# MIXR_Input_System_-_input.net
KiCad netlist of a schematic drawn in Altium Designer
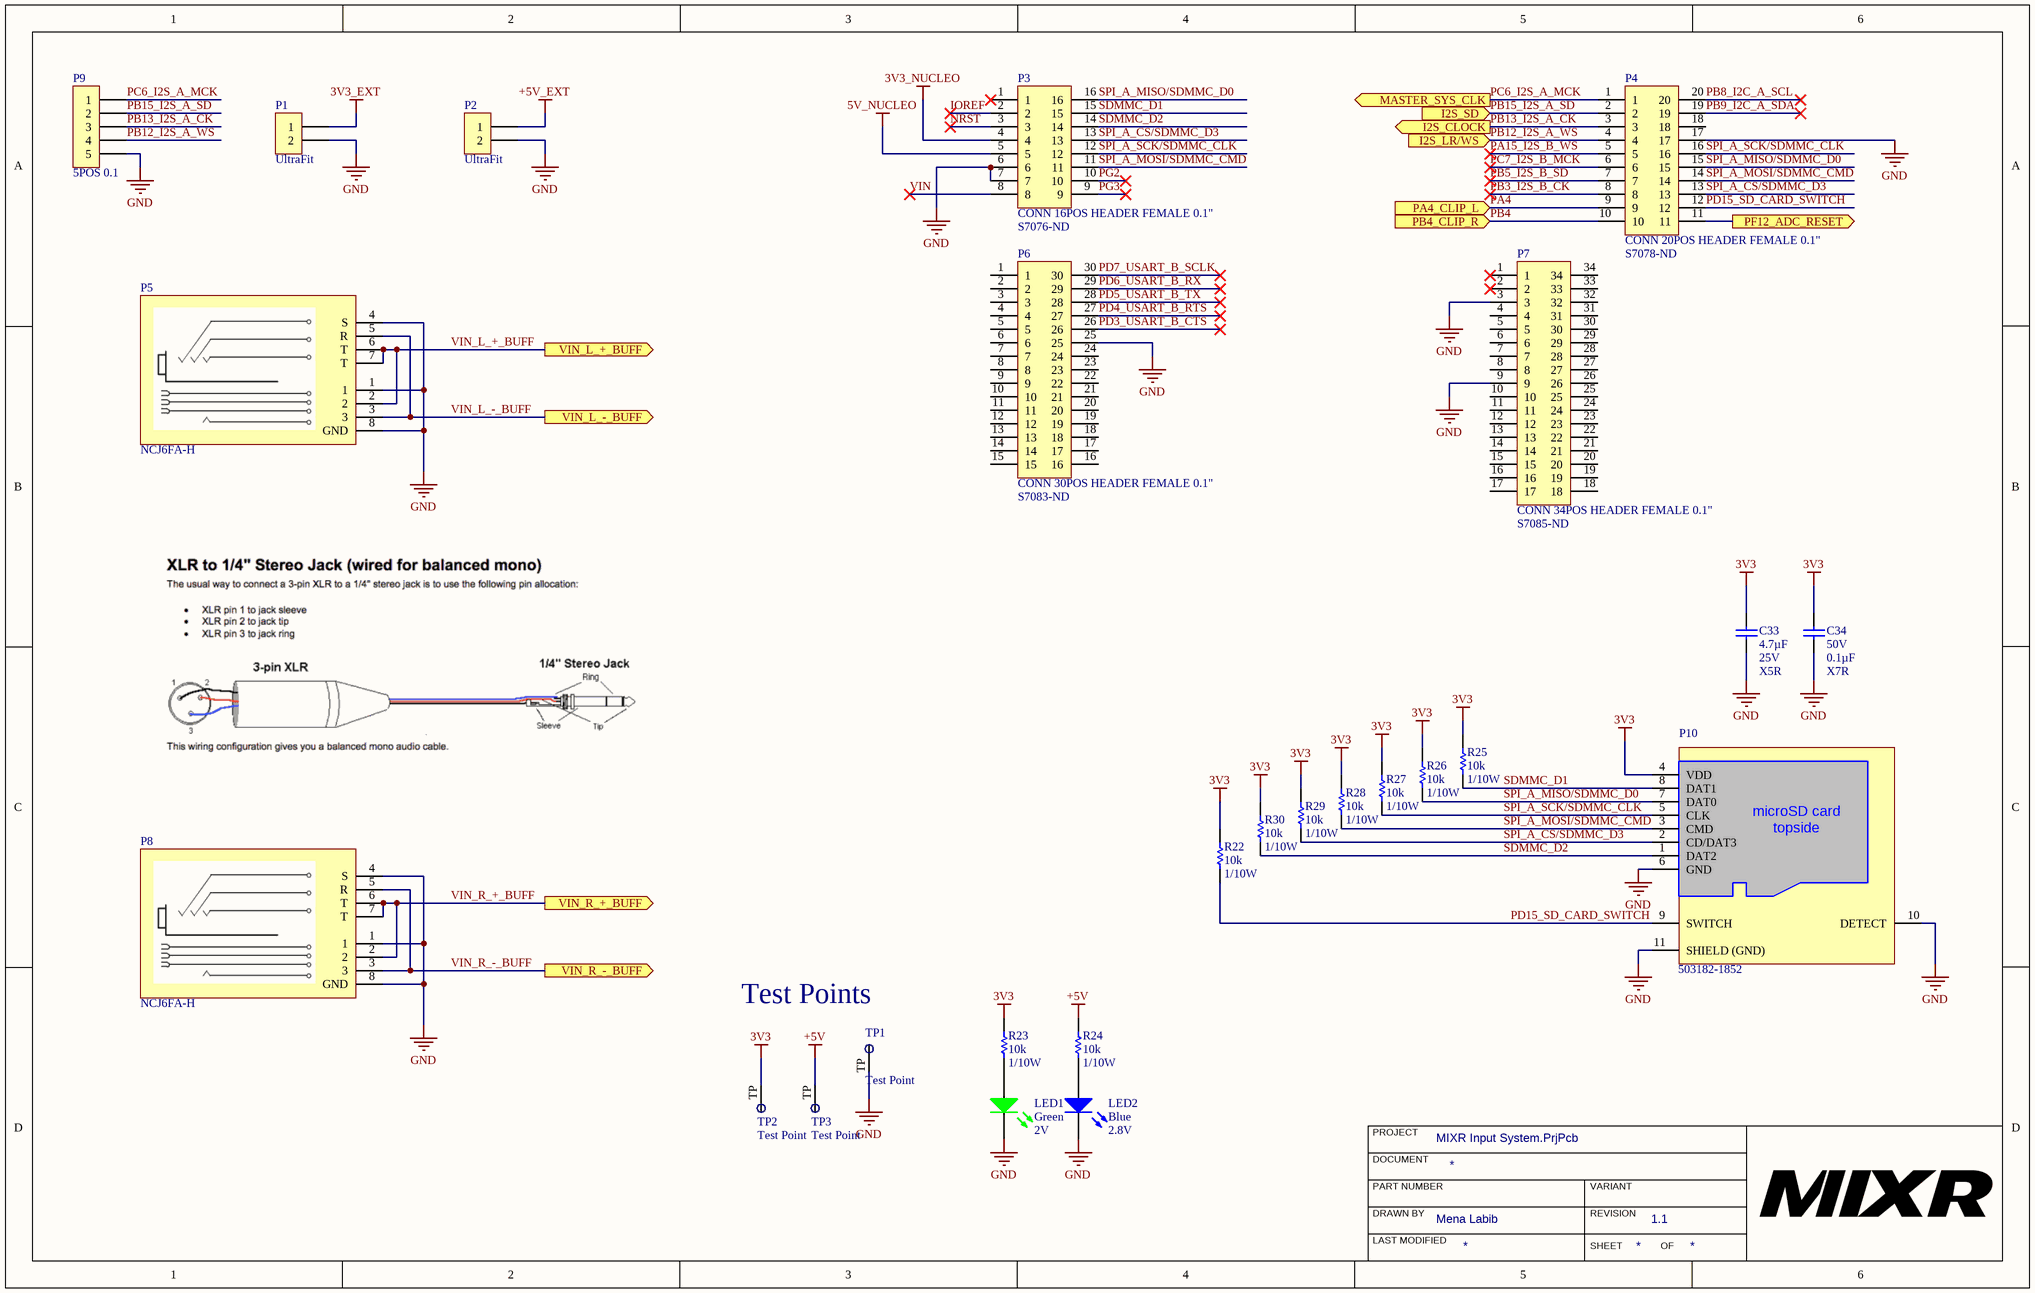
[diagram p0: MIXR Input System - input.SchDoc]

(export (version "E")
  (design (tool "Eeschema 10.0.6"))
  (components
    (comp (ref "C33")
      (value "CAP CER 4.7UF 25V 10% X5R 0603")
      (footprint "CAP, 0603")
      (description "4.7µF ±10% 25V Ceramic Capacitor X5R 0603 (1608 Metric)")
      (fields
        (field (name "TOLERANCE") "±10%")
        (field (name "CAPACITANCE") "4.7µF")
        (field (name "VOLTAGE") "25V")
        (field (name "TEMPERATURE COEFFICIENT") "X5R")
      )
      (libsource (lib "Schematic Diagrams") (part "CAP CER 4.7UF 25V 10% X5R 0603"))
    )
    (comp (ref "C34")
      (value "CAP CER 0.1UF 50V 10% X7R 0603")
      (footprint "CAP, 0603")
      (description "0.10µF ±10% 50V Ceramic Capacitor X7R 0603 (1608 Metric)")
      (fields
        (field (name "VOLTAGE") "50V")
        (field (name "TOLERANCE") "±10%")
        (field (name "CAPACITANCE") "0.1µF")
        (field (name "TEMPERATURE COEFFICIENT") "X7R")
      )
      (libsource (lib "Schematic Diagrams") (part "CAP CER 0.1UF 50V 10% X7R 0603"))
    )
    (comp (ref "LED1")
      (value "LED GREEN CLEAR 2V 0603")
      (footprint "LED_0603")
      (description "Green 572nm LED Indication - Discrete 2V 0603 (1608 Metric)")
      (fields
        (field (name "MANUFACTURER") "Wurth Electronics Inc.")
        (field (name "MANUFACTURER PART NUMBER") "150060VS75000")
        (field (name "COLOR") "Green")
        (field (name "VOLTAGE - FORWARD (VF) (TYP)") "2V")
      )
      (libsource (lib "Schematic Diagrams") (part "LED GREEN CLEAR 2V 0603"))
    )
    (comp (ref "LED2")
      (value "LED BLUE CLEAR 2.8V 0603")
      (footprint "LED_0603")
      (description "Blue 470nm LED Indication - Discrete 2.8V 0603 (1608 Metric)")
      (fields (field (name "COLOR") "Blue") (field (name "VOLTAGE - FORWARD (VF) (TYP)") "2.8V"))
      (libsource (lib "Schematic Diagrams") (part "LED BLUE CLEAR 2.8V 0603"))
    )
    (comp (ref "P1")
      (value "CONN 2POS ULTRA-FIT 0.138\"")
      (footprint "CONN, 2POS ULTRA-FIT")
      (description "Connector Header Through Hole 2 position 0.138\" (3.50mm)")
      (fields
        (field (name "MANUFACTURER") "Molex")
        (field (name "MANUFACTURER PART NUMBER") "1722871102")
        (field (name "SERIES") "UltraFit")
      )
      (libsource (lib "Schematic Diagrams") (part "CONN 2POS ULTRA-FIT 0.138{dblquote}"))
    )
    (comp (ref "P2")
      (value "CONN 2POS ULTRA-FIT 0.138\"")
      (footprint "CONN, 2POS ULTRA-FIT")
      (description "Connector Header Through Hole 2 position 0.138\" (3.50mm)")
      (fields
        (field (name "MANUFACTURER") "Molex")
        (field (name "MANUFACTURER PART NUMBER") "1722871102")
        (field (name "SERIES") "UltraFit")
      )
      (libsource (lib "Schematic Diagrams") (part "CONN 2POS ULTRA-FIT 0.138{dblquote}"))
    )
    (comp (ref "P3")
      (value "CONN 16POS HEADER FEMALE 0.1\"")
      (footprint "CONN, 16POS 0.100\" Header")
      (description "16 Position Header Connector 0.100\" (2.54mm) Through Hole Tin")
      (fields
        (field (name "MANUFACTURER") "Sullins")
        (field (name "MANUFACTURER PART NUMBER") "PPTC082LFBN-RC")
        (field (name "SUPPLIER PART NUMBER 1") "S7076-ND")
      )
      (libsource (lib "Schematic Diagrams") (part "CONN 16POS HEADER FEMALE 0.1{dblquote}"))
    )
    (comp (ref "P4")
      (value "CONN 20POS HEADER FEMALE 0.1\"")
      (footprint "CONN, 20POS 0.100\" HEADER")
      (description "20 Position Header Connector 0.100\" (2.54mm) Through Hole Tin")
      (fields
        (field (name "MANUFACTURER") "Sullins")
        (field (name "MANUFACTURER PART NUMBER") "PPTC102LFBN-RC")
        (field (name "SUPPLIER PART NUMBER 1") "S7078-ND")
      )
      (libsource (lib "Schematic Diagrams") (part "CONN 20POS HEADER FEMALE 0.1{dblquote}"))
    )
    (comp (ref "P5")
      (value "CONN XLR-TRS COMBO 3 POLE")
      (footprint "CONN XLR-TRS COMBO 3 POLE")
      (description "XLR Connectors A SERIES COMBO;3POLE FEM;PCB HOR")
      (fields
        (field (name "MANUFACTURER_PART_NUMBER") "NCJ6FA-H")
        (field (name "MOUSER PART NUMBER") "568-NCJ6FA-H")
        (field (name "MANUFACTURER PART NUMBER") "NCJ6FA-H")
      )
      (libsource (lib "Schematic Diagrams") (part "CONN XLR-TRS COMBO 3 POLE"))
    )
    (comp (ref "P6")
      (value "CONN 30POS HEADER FEMALE 0.1\"")
      (footprint "CONN, 30POS 0.100\" HEADER")
      (description "30 Position Header Connector 0.100\" (2.54mm) Through Hole Tin")
      (fields
        (field (name "MANUFACTURER") "Sullins")
        (field (name "MANUFACTURER PART NUMBER") "PPTC152LFBN-RC")
        (field (name "SUPPLIER PART NUMBER 1") "S7083-ND")
      )
      (libsource (lib "Schematic Diagrams") (part "CONN 30POS HEADER FEMALE 0.1{dblquote}"))
    )
    (comp (ref "P7")
      (value "CONN 34POS HEADER FEMALE 0.1\"")
      (footprint "CONN, 34POS 0.100\" HEADER")
      (description "34 Position Header Connector 0.100\" (2.54mm) Through Hole Tin")
      (fields
        (field (name "MANUFACTURER") "Sullins")
        (field (name "MANUFACTURER PART NUMBER") "PPTC172LFBN-RC")
        (field (name "SUPPLIER PART NUMBER 1") "S7085-ND")
      )
      (libsource (lib "Schematic Diagrams") (part "CONN 34POS HEADER FEMALE 0.1{dblquote}"))
    )
    (comp (ref "P8")
      (value "CONN XLR-TRS COMBO 3 POLE")
      (footprint "CONN XLR-TRS COMBO 3 POLE")
      (description "XLR Connectors A SERIES COMBO;3POLE FEM;PCB HOR")
      (fields
        (field (name "MANUFACTURER_PART_NUMBER") "NCJ6FA-H")
        (field (name "MOUSER PART NUMBER") "568-NCJ6FA-H")
        (field (name "MANUFACTURER PART NUMBER") "NCJ6FA-H")
      )
      (libsource (lib "Schematic Diagrams") (part "CONN XLR-TRS COMBO 3 POLE"))
    )
    (comp (ref "P9")
      (value "5POS 0.1")
      (footprint "CONN, 5POS HEADR 0.1\"")
      (description "5 Positions Header, Breakaway Connector 0.100\" (2.54mm) Through Hole Tin")
      (libsource (lib "Schematic Diagrams") (part "CONN 5POS HEADR MALE 0.1in"))
    )
    (comp (ref "P10")
      (value "CONN MICRO-SD ULTRA-LOW 8CKT")
      (footprint "CONN MICRO-SD HOLDER MOLEX 503182-1852")
      (description "9 (8 + 1) Position Card Connector microSD™ Surface Mount, Right Angle Gold")
      (fields (field (name "MANUFACTURER") "Molex") (field (name "MANUFACTURER PART NUMBER") "503182-1852"))
      (libsource (lib "Schematic Diagrams") (part "CONN MICRO-SD ULTRA-LOW 8CKT"))
    )
    (comp (ref "R22")
      (value "RES 10K OHM 1% 1/10W 0603")
      (footprint "RES, 0603")
      (description "RES SMD 10K OHM 1% 1/10W 0603")
      (fields
        (field (name "TOLERANCE") "±1%")
        (field (name "RESISTANCE") "10k")
        (field (name "POWER") "1/10W")
      )
      (libsource (lib "Schematic Diagrams") (part "RES 10K OHM 1% 1/10W 0603"))
    )
    (comp (ref "R23")
      (value "RES 10K OHM 1% 1/10W 0603")
      (footprint "RES, 0603")
      (description "RES SMD 10K OHM 1% 1/10W 0603")
      (fields
        (field (name "TOLERANCE") "±1%")
        (field (name "RESISTANCE") "10k")
        (field (name "POWER") "1/10W")
      )
      (libsource (lib "Schematic Diagrams") (part "RES 10K OHM 1% 1/10W 0603"))
    )
    (comp (ref "R24")
      (value "RES 10K OHM 1% 1/10W 0603")
      (footprint "RES, 0603")
      (description "RES SMD 10K OHM 1% 1/10W 0603")
      (fields
        (field (name "TOLERANCE") "±1%")
        (field (name "RESISTANCE") "10k")
        (field (name "POWER") "1/10W")
      )
      (libsource (lib "Schematic Diagrams") (part "RES 10K OHM 1% 1/10W 0603"))
    )
    (comp (ref "R25")
      (value "RES 10K OHM 1% 1/10W 0603")
      (footprint "RES, 0603")
      (description "RES SMD 10K OHM 1% 1/10W 0603")
      (fields
        (field (name "TOLERANCE") "±1%")
        (field (name "RESISTANCE") "10k")
        (field (name "POWER") "1/10W")
      )
      (libsource (lib "Schematic Diagrams") (part "RES 10K OHM 1% 1/10W 0603"))
    )
    (comp (ref "R26")
      (value "RES 10K OHM 1% 1/10W 0603")
      (footprint "RES, 0603")
      (description "RES SMD 10K OHM 1% 1/10W 0603")
      (fields
        (field (name "TOLERANCE") "±1%")
        (field (name "RESISTANCE") "10k")
        (field (name "POWER") "1/10W")
      )
      (libsource (lib "Schematic Diagrams") (part "RES 10K OHM 1% 1/10W 0603"))
    )
    (comp (ref "R27")
      (value "RES 10K OHM 1% 1/10W 0603")
      (footprint "RES, 0603")
      (description "RES SMD 10K OHM 1% 1/10W 0603")
      (fields
        (field (name "TOLERANCE") "±1%")
        (field (name "RESISTANCE") "10k")
        (field (name "POWER") "1/10W")
      )
      (libsource (lib "Schematic Diagrams") (part "RES 10K OHM 1% 1/10W 0603"))
    )
    (comp (ref "R28")
      (value "RES 10K OHM 1% 1/10W 0603")
      (footprint "RES, 0603")
      (description "RES SMD 10K OHM 1% 1/10W 0603")
      (fields
        (field (name "TOLERANCE") "±1%")
        (field (name "RESISTANCE") "10k")
        (field (name "POWER") "1/10W")
      )
      (libsource (lib "Schematic Diagrams") (part "RES 10K OHM 1% 1/10W 0603"))
    )
    (comp (ref "R29")
      (value "RES 10K OHM 1% 1/10W 0603")
      (footprint "RES, 0603")
      (description "RES SMD 10K OHM 1% 1/10W 0603")
      (fields
        (field (name "TOLERANCE") "±1%")
        (field (name "RESISTANCE") "10k")
        (field (name "POWER") "1/10W")
      )
      (libsource (lib "Schematic Diagrams") (part "RES 10K OHM 1% 1/10W 0603"))
    )
    (comp (ref "R30")
      (value "RES 10K OHM 1% 1/10W 0603")
      (footprint "RES, 0603")
      (description "RES SMD 10K OHM 1% 1/10W 0603")
      (fields
        (field (name "TOLERANCE") "±1%")
        (field (name "RESISTANCE") "10k")
        (field (name "POWER") "1/10W")
      )
      (libsource (lib "Schematic Diagrams") (part "RES 10K OHM 1% 1/10W 0603"))
    )
    (comp (ref "TP1")
      (value "Test Point")
      (footprint "Test Point")
      (libsource (lib "Schematic Diagrams") (part "Test Point"))
    )
    (comp (ref "TP2")
      (value "Test Point")
      (footprint "Test Point")
      (libsource (lib "Schematic Diagrams") (part "Test Point"))
    )
    (comp (ref "TP3")
      (value "Test Point")
      (footprint "Test Point")
      (libsource (lib "Schematic Diagrams") (part "Test Point"))
    )
  )
  (nets
    (net (code "1") (name "+5V") (class "Default")
      (node (ref "R24") (pin "1") (pinfunction "1_1") (pintype "passive"))
      (node (ref "TP3") (pin "TP") (pinfunction "1_TP") (pintype "passive"))
    )
    (net (code "2") (name "+5V_EXT") (class "Default")
      (node (ref "P2") (pin "1") (pinfunction "1_1") (pintype "passive"))
    )
    (net (code "3") (name "/IOREF") (class "Default")
      (node (ref "P3") (pin "2") (pinfunction "2_2") (pintype "passive+no_connect"))
    )
    (net (code "4") (name "/NRST") (class "Default")
      (node (ref "P3") (pin "3") (pinfunction "3_3") (pintype "passive+no_connect"))
    )
    (net (code "5") (name "/PA4") (class "Default")
      (node (ref "P4") (pin "9") (pinfunction "9_9") (pintype "passive"))
    )
    (net (code "6") (name "/PA15_I2S_B_WS") (class "Default")
      (node (ref "P4") (pin "5") (pinfunction "5_5") (pintype "passive+no_connect"))
    )
    (net (code "7") (name "/PB3_I2S_B_CK") (class "Default")
      (node (ref "P4") (pin "8") (pinfunction "8_8") (pintype "passive+no_connect"))
    )
    (net (code "8") (name "/PB4") (class "Default")
      (node (ref "P4") (pin "10") (pinfunction "10_10") (pintype "passive"))
    )
    (net (code "9") (name "/PB5_I2S_B_SD") (class "Default")
      (node (ref "P4") (pin "7") (pinfunction "7_7") (pintype "passive+no_connect"))
    )
    (net (code "10") (name "/PB8_I2C_A_SCL") (class "Default")
      (node (ref "P4") (pin "20") (pinfunction "20_20") (pintype "passive+no_connect"))
    )
    (net (code "11") (name "/PB9_I2C_A_SDA") (class "Default")
      (node (ref "P4") (pin "19") (pinfunction "19_19") (pintype "passive+no_connect"))
    )
    (net (code "12") (name "/PB12_I2S_A_WS") (class "Default")
      (node (ref "P4") (pin "4") (pinfunction "4_4") (pintype "passive"))
      (node (ref "P9") (pin "4") (pinfunction "4_4") (pintype "passive"))
    )
    (net (code "13") (name "/PB13_I2S_A_CK") (class "Default")
      (node (ref "P4") (pin "3") (pinfunction "3_3") (pintype "passive"))
      (node (ref "P9") (pin "3") (pinfunction "3_3") (pintype "passive"))
    )
    (net (code "14") (name "/PB15_I2S_A_SD") (class "Default")
      (node (ref "P4") (pin "2") (pinfunction "2_2") (pintype "passive"))
      (node (ref "P9") (pin "2") (pinfunction "2_2") (pintype "passive"))
    )
    (net (code "15") (name "/PC6_I2S_A_MCK") (class "Default")
      (node (ref "P4") (pin "1") (pinfunction "1_1") (pintype "passive"))
      (node (ref "P9") (pin "1") (pinfunction "1_1") (pintype "passive"))
    )
    (net (code "16") (name "/PC7_I2S_B_MCK") (class "Default")
      (node (ref "P4") (pin "6") (pinfunction "6_6") (pintype "passive+no_connect"))
    )
    (net (code "17") (name "/PD3_USART_B_CTS") (class "Default")
      (node (ref "P6") (pin "26") (pinfunction "26_26") (pintype "passive+no_connect"))
    )
    (net (code "18") (name "/PD4_USART_B_RTS") (class "Default")
      (node (ref "P6") (pin "27") (pinfunction "27_27") (pintype "passive+no_connect"))
    )
    (net (code "19") (name "/PD5_USART_B_TX") (class "Default")
      (node (ref "P6") (pin "28") (pinfunction "28_28") (pintype "passive+no_connect"))
    )
    (net (code "20") (name "/PD6_USART_B_RX") (class "Default")
      (node (ref "P6") (pin "29") (pinfunction "29_29") (pintype "passive+no_connect"))
    )
    (net (code "21") (name "/PD7_USART_B_SCLK") (class "Default")
      (node (ref "P6") (pin "30") (pinfunction "30_30") (pintype "passive+no_connect"))
    )
    (net (code "22") (name "/PD15_SD_CARD_SWITCH") (class "Default")
      (node (ref "P10") (pin "9") (pinfunction "SWITCH_9") (pintype "passive"))
      (node (ref "P4") (pin "12") (pinfunction "12_12") (pintype "passive"))
      (node (ref "R22") (pin "1") (pinfunction "1_1") (pintype "passive"))
    )
    (net (code "23") (name "/PF12_ADC_RESET") (class "Default")
      (node (ref "P4") (pin "11") (pinfunction "11_11") (pintype "passive"))
    )
    (net (code "24") (name "/PG2") (class "Default")
      (node (ref "P3") (pin "10") (pinfunction "10_10") (pintype "passive+no_connect"))
    )
    (net (code "25") (name "/PG3") (class "Default")
      (node (ref "P3") (pin "9") (pinfunction "9_9") (pintype "passive+no_connect"))
    )
    (net (code "26") (name "/SDMMC_D1") (class "Default")
      (node (ref "P10") (pin "8") (pinfunction "DAT1_8") (pintype "passive"))
      (node (ref "P3") (pin "15") (pinfunction "15_15") (pintype "passive"))
      (node (ref "R25") (pin "1") (pinfunction "1_1") (pintype "passive"))
    )
    (net (code "27") (name "/SDMMC_D2") (class "Default")
      (node (ref "P10") (pin "1") (pinfunction "DAT2_1") (pintype "passive"))
      (node (ref "P3") (pin "14") (pinfunction "14_14") (pintype "passive"))
      (node (ref "R30") (pin "1") (pinfunction "1_1") (pintype "passive"))
    )
    (net (code "28") (name "/SPI_A_CS{slash}SDMMC_D3") (class "Default")
      (node (ref "P10") (pin "2") (pinfunction "CD/DAT3_2") (pintype "passive"))
      (node (ref "P3") (pin "13") (pinfunction "13_13") (pintype "passive"))
      (node (ref "P4") (pin "13") (pinfunction "13_13") (pintype "passive"))
      (node (ref "R29") (pin "1") (pinfunction "1_1") (pintype "passive"))
    )
    (net (code "29") (name "/SPI_A_MISO{slash}SDMMC_D0") (class "Default")
      (node (ref "P10") (pin "7") (pinfunction "DAT0_7") (pintype "passive"))
      (node (ref "P3") (pin "16") (pinfunction "16_16") (pintype "passive"))
      (node (ref "P4") (pin "15") (pinfunction "15_15") (pintype "passive"))
      (node (ref "R26") (pin "1") (pinfunction "1_1") (pintype "passive"))
    )
    (net (code "30") (name "/SPI_A_MOSI{slash}SDMMC_CMD") (class "Default")
      (node (ref "P10") (pin "3") (pinfunction "CMD_3") (pintype "passive"))
      (node (ref "P3") (pin "11") (pinfunction "11_11") (pintype "passive"))
      (node (ref "P4") (pin "14") (pinfunction "14_14") (pintype "passive"))
      (node (ref "R28") (pin "1") (pinfunction "1_1") (pintype "passive"))
    )
    (net (code "31") (name "/SPI_A_SCK{slash}SDMMC_CLK") (class "Default")
      (node (ref "P10") (pin "5") (pinfunction "CLK_5") (pintype "passive"))
      (node (ref "P3") (pin "12") (pinfunction "12_12") (pintype "passive"))
      (node (ref "P4") (pin "16") (pinfunction "16_16") (pintype "passive"))
      (node (ref "R27") (pin "1") (pinfunction "1_1") (pintype "passive"))
    )
    (net (code "32") (name "/VIN") (class "Default")
      (node (ref "P3") (pin "8") (pinfunction "8_8") (pintype "passive+no_connect"))
    )
    (net (code "33") (name "/VIN_L_+_BUFF") (class "Default")
      (node (ref "P5") (pin "2") (pinfunction "2_2") (pintype "passive"))
      (node (ref "P5") (pin "6") (pinfunction "T_6") (pintype "passive"))
      (node (ref "P5") (pin "7") (pinfunction "T_7") (pintype "passive"))
    )
    (net (code "34") (name "/VIN_L_-_BUFF") (class "Default")
      (node (ref "P5") (pin "3") (pinfunction "3_3") (pintype "passive"))
      (node (ref "P5") (pin "5") (pinfunction "R_5") (pintype "passive"))
    )
    (net (code "35") (name "/VIN_R_+_BUFF") (class "Default")
      (node (ref "P8") (pin "2") (pinfunction "2_2") (pintype "passive"))
      (node (ref "P8") (pin "6") (pinfunction "T_6") (pintype "passive"))
      (node (ref "P8") (pin "7") (pinfunction "T_7") (pintype "passive"))
    )
    (net (code "36") (name "/VIN_R_-_BUFF") (class "Default")
      (node (ref "P8") (pin "3") (pinfunction "3_3") (pintype "passive"))
      (node (ref "P8") (pin "5") (pinfunction "R_5") (pintype "passive"))
    )
    (net (code "37") (name "3V3") (class "Default")
      (node (ref "C33") (pin "1") (pinfunction "1_1") (pintype "passive"))
      (node (ref "C34") (pin "2") (pinfunction "2_2") (pintype "passive"))
      (node (ref "P10") (pin "4") (pinfunction "VDD_4") (pintype "passive"))
      (node (ref "R22") (pin "2") (pinfunction "2_2") (pintype "passive"))
      (node (ref "R23") (pin "1") (pinfunction "1_1") (pintype "passive"))
      (node (ref "R25") (pin "2") (pinfunction "2_2") (pintype "passive"))
      (node (ref "R26") (pin "2") (pinfunction "2_2") (pintype "passive"))
      (node (ref "R27") (pin "2") (pinfunction "2_2") (pintype "passive"))
      (node (ref "R28") (pin "2") (pinfunction "2_2") (pintype "passive"))
      (node (ref "R29") (pin "2") (pinfunction "2_2") (pintype "passive"))
      (node (ref "R30") (pin "2") (pinfunction "2_2") (pintype "passive"))
      (node (ref "TP2") (pin "TP") (pinfunction "1_TP") (pintype "passive"))
    )
    (net (code "38") (name "3V3_EXT") (class "Default")
      (node (ref "P1") (pin "1") (pinfunction "1_1") (pintype "passive"))
    )
    (net (code "39") (name "3V3_NUCLEO") (class "Default")
      (node (ref "P3") (pin "4") (pinfunction "4_4") (pintype "passive"))
    )
    (net (code "40") (name "5V_NUCLEO") (class "Default")
      (node (ref "P3") (pin "5") (pinfunction "5_5") (pintype "passive"))
    )
    (net (code "41") (name "GND") (class "Default")
      (node (ref "C33") (pin "2") (pinfunction "2_2") (pintype "passive"))
      (node (ref "C34") (pin "1") (pinfunction "1_1") (pintype "passive"))
      (node (ref "LED1") (pin "2") (pinfunction "K_2") (pintype "passive"))
      (node (ref "LED2") (pin "2") (pinfunction "K_2") (pintype "passive"))
      (node (ref "P1") (pin "2") (pinfunction "2_2") (pintype "passive"))
      (node (ref "P10") (pin "10") (pinfunction "DETECT_10") (pintype "passive"))
      (node (ref "P10") (pin "11") (pinfunction "SHIELD_(GND)_11") (pintype "passive"))
      (node (ref "P10") (pin "6") (pinfunction "GND_6") (pintype "passive"))
      (node (ref "P2") (pin "2") (pinfunction "2_2") (pintype "passive"))
      (node (ref "P3") (pin "6") (pinfunction "6_6") (pintype "passive"))
      (node (ref "P3") (pin "7") (pinfunction "7_7") (pintype "passive"))
      (node (ref "P4") (pin "17") (pinfunction "17_17") (pintype "passive"))
      (node (ref "P5") (pin "1") (pinfunction "1_1") (pintype "passive"))
      (node (ref "P5") (pin "4") (pinfunction "S_4") (pintype "passive"))
      (node (ref "P5") (pin "8") (pinfunction "GND_8") (pintype "passive"))
      (node (ref "P6") (pin "25") (pinfunction "25_25") (pintype "passive"))
      (node (ref "P7") (pin "3") (pinfunction "3_3") (pintype "passive"))
      (node (ref "P7") (pin "9") (pinfunction "9_9") (pintype "passive"))
      (node (ref "P8") (pin "1") (pinfunction "1_1") (pintype "passive"))
      (node (ref "P8") (pin "4") (pinfunction "S_4") (pintype "passive"))
      (node (ref "P8") (pin "8") (pinfunction "GND_8") (pintype "passive"))
      (node (ref "P9") (pin "5") (pinfunction "5_5") (pintype "passive"))
      (node (ref "TP1") (pin "TP") (pinfunction "1_TP") (pintype "passive"))
    )
    (net (code "42") (name "Net-(LED1-A)") (class "Default")
      (node (ref "LED1") (pin "1") (pinfunction "A_1") (pintype "passive"))
      (node (ref "R23") (pin "2") (pinfunction "2_2") (pintype "passive"))
    )
    (net (code "43") (name "Net-(LED2-A)") (class "Default")
      (node (ref "LED2") (pin "1") (pinfunction "A_1") (pintype "passive"))
      (node (ref "R24") (pin "2") (pinfunction "2_2") (pintype "passive"))
    )
    (net (code "44") (name "unconnected-(P3-Pad1)") (class "Default")
      (node (ref "P3") (pin "1") (pinfunction "1_1") (pintype "passive+no_connect"))
    )
    (net (code "45") (name "unconnected-(P4-Pad18)") (class "Default")
      (node (ref "P4") (pin "18") (pinfunction "18_18") (pintype "passive"))
    )
    (net (code "46") (name "unconnected-(P6-Pad1)") (class "Default")
      (node (ref "P6") (pin "1") (pinfunction "1_1") (pintype "passive"))
    )
    (net (code "47") (name "unconnected-(P6-Pad2)") (class "Default")
      (node (ref "P6") (pin "2") (pinfunction "2_2") (pintype "passive"))
    )
    (net (code "48") (name "unconnected-(P6-Pad3)") (class "Default")
      (node (ref "P6") (pin "3") (pinfunction "3_3") (pintype "passive"))
    )
    (net (code "49") (name "unconnected-(P6-Pad4)") (class "Default")
      (node (ref "P6") (pin "4") (pinfunction "4_4") (pintype "passive"))
    )
    (net (code "50") (name "unconnected-(P6-Pad5)") (class "Default")
      (node (ref "P6") (pin "5") (pinfunction "5_5") (pintype "passive"))
    )
    (net (code "51") (name "unconnected-(P6-Pad6)") (class "Default")
      (node (ref "P6") (pin "6") (pinfunction "6_6") (pintype "passive"))
    )
    (net (code "52") (name "unconnected-(P6-Pad7)") (class "Default")
      (node (ref "P6") (pin "7") (pinfunction "7_7") (pintype "passive"))
    )
    (net (code "53") (name "unconnected-(P6-Pad8)") (class "Default")
      (node (ref "P6") (pin "8") (pinfunction "8_8") (pintype "passive"))
    )
    (net (code "54") (name "unconnected-(P6-Pad9)") (class "Default")
      (node (ref "P6") (pin "9") (pinfunction "9_9") (pintype "passive"))
    )
    (net (code "55") (name "unconnected-(P6-Pad10)") (class "Default")
      (node (ref "P6") (pin "10") (pinfunction "10_10") (pintype "passive"))
    )
    (net (code "56") (name "unconnected-(P6-Pad11)") (class "Default")
      (node (ref "P6") (pin "11") (pinfunction "11_11") (pintype "passive"))
    )
    (net (code "57") (name "unconnected-(P6-Pad12)") (class "Default")
      (node (ref "P6") (pin "12") (pinfunction "12_12") (pintype "passive"))
    )
    (net (code "58") (name "unconnected-(P6-Pad13)") (class "Default")
      (node (ref "P6") (pin "13") (pinfunction "13_13") (pintype "passive"))
    )
    (net (code "59") (name "unconnected-(P6-Pad14)") (class "Default")
      (node (ref "P6") (pin "14") (pinfunction "14_14") (pintype "passive"))
    )
    (net (code "60") (name "unconnected-(P6-Pad15)") (class "Default")
      (node (ref "P6") (pin "15") (pinfunction "15_15") (pintype "passive"))
    )
    (net (code "61") (name "unconnected-(P6-Pad16)") (class "Default")
      (node (ref "P6") (pin "16") (pinfunction "16_16") (pintype "passive"))
    )
    (net (code "62") (name "unconnected-(P6-Pad17)") (class "Default")
      (node (ref "P6") (pin "17") (pinfunction "17_17") (pintype "passive"))
    )
    (net (code "63") (name "unconnected-(P6-Pad18)") (class "Default")
      (node (ref "P6") (pin "18") (pinfunction "18_18") (pintype "passive"))
    )
    (net (code "64") (name "unconnected-(P6-Pad19)") (class "Default")
      (node (ref "P6") (pin "19") (pinfunction "19_19") (pintype "passive"))
    )
    (net (code "65") (name "unconnected-(P6-Pad20)") (class "Default")
      (node (ref "P6") (pin "20") (pinfunction "20_20") (pintype "passive"))
    )
    (net (code "66") (name "unconnected-(P6-Pad21)") (class "Default")
      (node (ref "P6") (pin "21") (pinfunction "21_21") (pintype "passive"))
    )
    (net (code "67") (name "unconnected-(P6-Pad22)") (class "Default")
      (node (ref "P6") (pin "22") (pinfunction "22_22") (pintype "passive"))
    )
    (net (code "68") (name "unconnected-(P6-Pad23)") (class "Default")
      (node (ref "P6") (pin "23") (pinfunction "23_23") (pintype "passive"))
    )
    (net (code "69") (name "unconnected-(P6-Pad24)") (class "Default")
      (node (ref "P6") (pin "24") (pinfunction "24_24") (pintype "passive"))
    )
    (net (code "70") (name "unconnected-(P7-Pad1)") (class "Default")
      (node (ref "P7") (pin "1") (pinfunction "1_1") (pintype "passive+no_connect"))
    )
    (net (code "71") (name "unconnected-(P7-Pad2)") (class "Default")
      (node (ref "P7") (pin "2") (pinfunction "2_2") (pintype "passive+no_connect"))
    )
    (net (code "72") (name "unconnected-(P7-Pad4)") (class "Default")
      (node (ref "P7") (pin "4") (pinfunction "4_4") (pintype "passive"))
    )
    (net (code "73") (name "unconnected-(P7-Pad5)") (class "Default")
      (node (ref "P7") (pin "5") (pinfunction "5_5") (pintype "passive"))
    )
    (net (code "74") (name "unconnected-(P7-Pad6)") (class "Default")
      (node (ref "P7") (pin "6") (pinfunction "6_6") (pintype "passive"))
    )
    (net (code "75") (name "unconnected-(P7-Pad7)") (class "Default")
      (node (ref "P7") (pin "7") (pinfunction "7_7") (pintype "passive"))
    )
    (net (code "76") (name "unconnected-(P7-Pad8)") (class "Default")
      (node (ref "P7") (pin "8") (pinfunction "8_8") (pintype "passive"))
    )
    (net (code "77") (name "unconnected-(P7-Pad10)") (class "Default")
      (node (ref "P7") (pin "10") (pinfunction "10_10") (pintype "passive"))
    )
    (net (code "78") (name "unconnected-(P7-Pad11)") (class "Default")
      (node (ref "P7") (pin "11") (pinfunction "11_11") (pintype "passive"))
    )
    (net (code "79") (name "unconnected-(P7-Pad12)") (class "Default")
      (node (ref "P7") (pin "12") (pinfunction "12_12") (pintype "passive"))
    )
    (net (code "80") (name "unconnected-(P7-Pad13)") (class "Default")
      (node (ref "P7") (pin "13") (pinfunction "13_13") (pintype "passive"))
    )
    (net (code "81") (name "unconnected-(P7-Pad14)") (class "Default")
      (node (ref "P7") (pin "14") (pinfunction "14_14") (pintype "passive"))
    )
    (net (code "82") (name "unconnected-(P7-Pad15)") (class "Default")
      (node (ref "P7") (pin "15") (pinfunction "15_15") (pintype "passive"))
    )
    (net (code "83") (name "unconnected-(P7-Pad16)") (class "Default")
      (node (ref "P7") (pin "16") (pinfunction "16_16") (pintype "passive"))
    )
    (net (code "84") (name "unconnected-(P7-Pad17)") (class "Default")
      (node (ref "P7") (pin "17") (pinfunction "17_17") (pintype "passive"))
    )
    (net (code "85") (name "unconnected-(P7-Pad18)") (class "Default")
      (node (ref "P7") (pin "18") (pinfunction "18_18") (pintype "passive"))
    )
    (net (code "86") (name "unconnected-(P7-Pad19)") (class "Default")
      (node (ref "P7") (pin "19") (pinfunction "19_19") (pintype "passive"))
    )
    (net (code "87") (name "unconnected-(P7-Pad20)") (class "Default")
      (node (ref "P7") (pin "20") (pinfunction "20_20") (pintype "passive"))
    )
    (net (code "88") (name "unconnected-(P7-Pad21)") (class "Default")
      (node (ref "P7") (pin "21") (pinfunction "21_21") (pintype "passive"))
    )
    (net (code "89") (name "unconnected-(P7-Pad22)") (class "Default")
      (node (ref "P7") (pin "22") (pinfunction "22_22") (pintype "passive"))
    )
    (net (code "90") (name "unconnected-(P7-Pad23)") (class "Default")
      (node (ref "P7") (pin "23") (pinfunction "23_23") (pintype "passive"))
    )
    (net (code "91") (name "unconnected-(P7-Pad24)") (class "Default")
      (node (ref "P7") (pin "24") (pinfunction "24_24") (pintype "passive"))
    )
    (net (code "92") (name "unconnected-(P7-Pad25)") (class "Default")
      (node (ref "P7") (pin "25") (pinfunction "25_25") (pintype "passive"))
    )
    (net (code "93") (name "unconnected-(P7-Pad26)") (class "Default")
      (node (ref "P7") (pin "26") (pinfunction "26_26") (pintype "passive"))
    )
    (net (code "94") (name "unconnected-(P7-Pad27)") (class "Default")
      (node (ref "P7") (pin "27") (pinfunction "27_27") (pintype "passive"))
    )
    (net (code "95") (name "unconnected-(P7-Pad28)") (class "Default")
      (node (ref "P7") (pin "28") (pinfunction "28_28") (pintype "passive"))
    )
    (net (code "96") (name "unconnected-(P7-Pad29)") (class "Default")
      (node (ref "P7") (pin "29") (pinfunction "29_29") (pintype "passive"))
    )
    (net (code "97") (name "unconnected-(P7-Pad30)") (class "Default")
      (node (ref "P7") (pin "30") (pinfunction "30_30") (pintype "passive"))
    )
    (net (code "98") (name "unconnected-(P7-Pad31)") (class "Default")
      (node (ref "P7") (pin "31") (pinfunction "31_31") (pintype "passive"))
    )
    (net (code "99") (name "unconnected-(P7-Pad32)") (class "Default")
      (node (ref "P7") (pin "32") (pinfunction "32_32") (pintype "passive"))
    )
    (net (code "100") (name "unconnected-(P7-Pad33)") (class "Default")
      (node (ref "P7") (pin "33") (pinfunction "33_33") (pintype "passive"))
    )
    (net (code "101") (name "unconnected-(P7-Pad34)") (class "Default")
      (node (ref "P7") (pin "34") (pinfunction "34_34") (pintype "passive"))
    )
  )
)
